# attiny-breakout.net
KiCad netlist of a schematic drawn in EAGLE
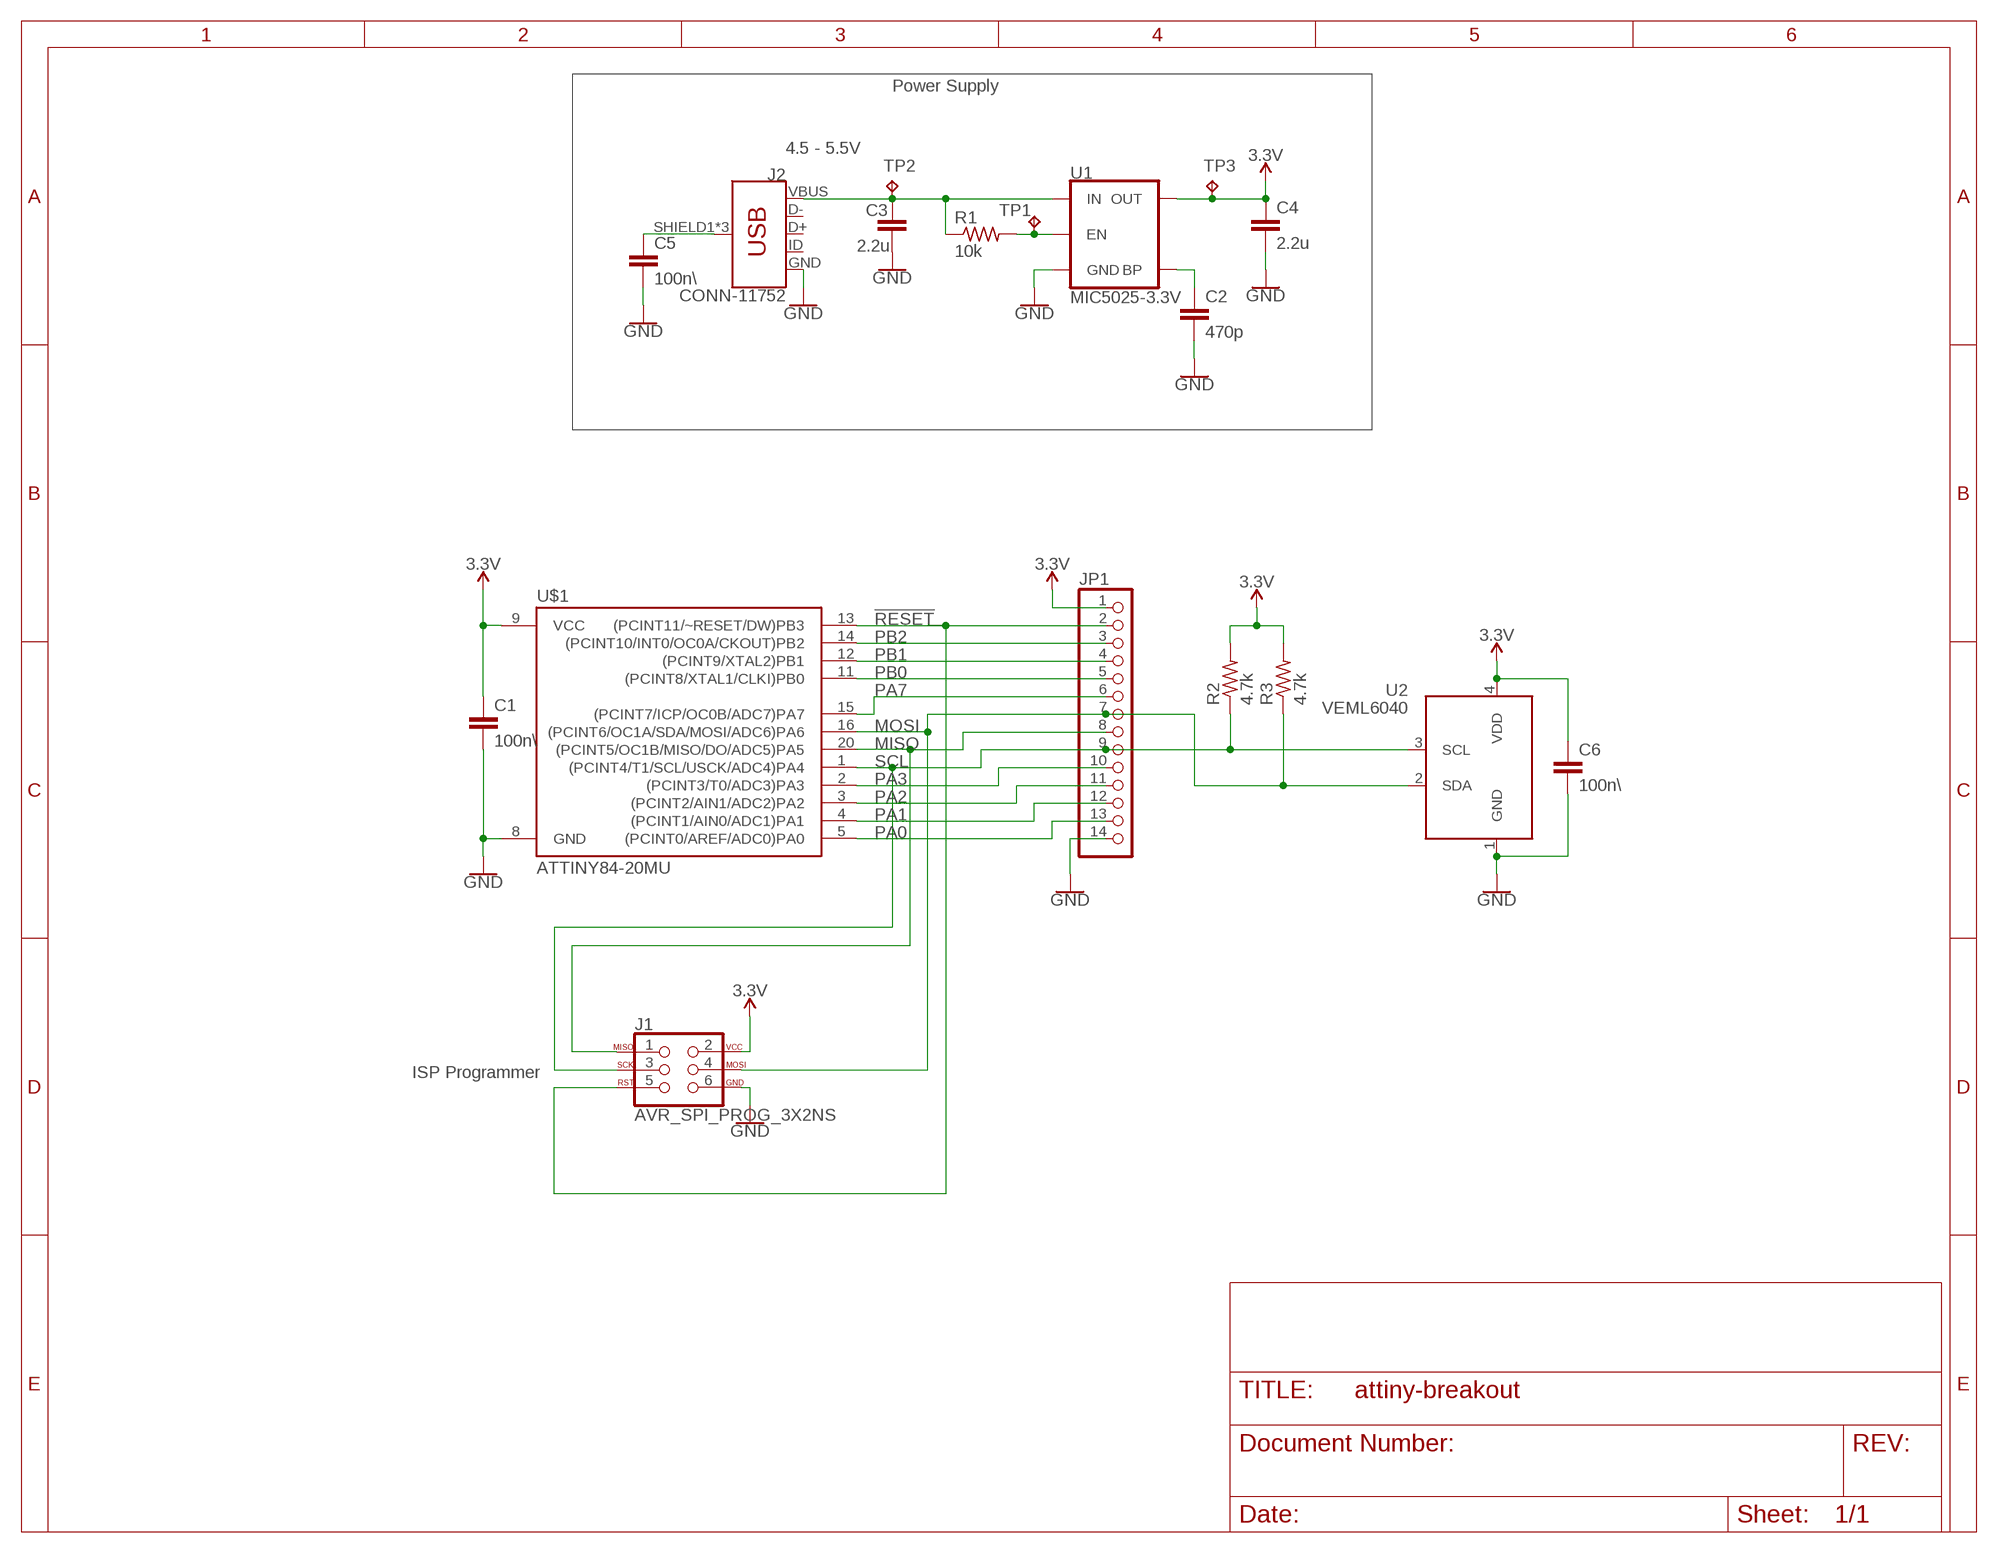
[diagram p0: schematic, sheet 1]

(export (version "E")
  (design (tool "Eeschema 10.0.6"))
  (components
    (comp (ref "C1")
      (value "100n\\")
      (footprint "eagle-import:C0805")
      (libsource (lib "eagle-import") (part "C-EUC0805"))
    )
    (comp (ref "C2")
      (value "470p")
      (footprint "eagle-import:C0805")
      (libsource (lib "eagle-import") (part "C-EUC0805"))
    )
    (comp (ref "C3")
      (value "2.2u")
      (footprint "eagle-import:C0805")
      (libsource (lib "eagle-import") (part "C-EUC0805"))
    )
    (comp (ref "C4")
      (value "2.2u")
      (footprint "eagle-import:C0805")
      (libsource (lib "eagle-import") (part "C-EUC0805"))
    )
    (comp (ref "C5")
      (value "100n\\")
      (footprint "eagle-import:C0805")
      (libsource (lib "eagle-import") (part "C-EUC0805"))
    )
    (comp (ref "C6")
      (value "100n\\")
      (footprint "eagle-import:C0805")
      (libsource (lib "eagle-import") (part "C-EUC0805"))
    )
    (comp (ref "J1")
      (value "AVR_SPI_PROG_3X2NS")
      (footprint "eagle-import:2X3-NS")
      (libsource (lib "eagle-import") (part "AVR_SPI_PROG_3X2NS"))
    )
    (comp (ref "J2")
      (value "CONN-11752")
      (footprint "eagle-import:USB-B-MICRO-SMD")
      (libsource (lib "eagle-import") (part "USB_MICRO-B_FEMALE-SMT"))
    )
    (comp (ref "JP1")
      (value "PINHD-1X14")
      (footprint "eagle-import:1X14")
      (libsource (lib "eagle-import") (part "PINHD-1X14"))
    )
    (comp (ref "R1")
      (value "10k")
      (footprint "eagle-import:R0805")
      (libsource (lib "eagle-import") (part "R-US_R0805"))
    )
    (comp (ref "R2")
      (value "4.7k")
      (footprint "eagle-import:R0805")
      (libsource (lib "eagle-import") (part "R-US_R0805"))
    )
    (comp (ref "R3")
      (value "4.7k")
      (footprint "eagle-import:R0805")
      (libsource (lib "eagle-import") (part "R-US_R0805"))
    )
    (comp (ref "TP1")
      (value "TPPAD1-13")
      (footprint "eagle-import:P1-13")
      (libsource (lib "eagle-import") (part "TPPAD1-13"))
    )
    (comp (ref "TP2")
      (value "TPPAD1-13")
      (footprint "eagle-import:P1-13")
      (libsource (lib "eagle-import") (part "TPPAD1-13"))
    )
    (comp (ref "TP3")
      (value "TPPAD1-13")
      (footprint "eagle-import:P1-13")
      (libsource (lib "eagle-import") (part "TPPAD1-13"))
    )
    (comp (ref "U$1")
      (value "ATTINY84-20MU")
      (footprint "eagle-import:QFN20")
      (libsource (lib "eagle-import") (part "ATTINY84ATTINY84-20MU"))
    )
    (comp (ref "U1")
      (value "MIC5025-3.3V")
      (footprint "eagle-import:SOT23-5")
      (libsource (lib "eagle-import") (part "V_REG_MIC52053.3V"))
    )
    (comp (ref "U2")
      (value "VEML6040")
      (footprint "eagle-import:VEML6040")
      (libsource (lib "eagle-import") (part "VEML6040"))
    )
  )
  (nets
    (net (code "1") (name "/MISO") (class "Default")
      (node (ref "J1") (pin "1") (pinfunction "1_1") (pintype "passive"))
      (node (ref "JP1") (pin "8") (pinfunction "8_8") (pintype "passive"))
      (node (ref "U$1") (pin "20") (pinfunction "(PCINT5/OC1B/MISO/DO/ADC5)PA5_20") (pintype "bidirectional"))
    )
    (net (code "2") (name "/MOSI") (class "Default")
      (node (ref "J1") (pin "4") (pinfunction "4_4") (pintype "passive"))
      (node (ref "JP1") (pin "7") (pinfunction "7_7") (pintype "passive"))
      (node (ref "R3") (pin "1") (pinfunction "1_1") (pintype "passive"))
      (node (ref "U$1") (pin "16") (pinfunction "(PCINT6/OC1A/SDA/MOSI/ADC6)PA6_16") (pintype "bidirectional"))
      (node (ref "U2") (pin "2") (pinfunction "SDA_2") (pintype "bidirectional"))
    )
    (net (code "3") (name "/PA0") (class "Default")
      (node (ref "JP1") (pin "13") (pinfunction "13_13") (pintype "passive"))
      (node (ref "U$1") (pin "5") (pinfunction "(PCINT0/AREF/ADC0)PA0_5") (pintype "bidirectional"))
    )
    (net (code "4") (name "/PA1") (class "Default")
      (node (ref "JP1") (pin "12") (pinfunction "12_12") (pintype "passive"))
      (node (ref "U$1") (pin "4") (pinfunction "(PCINT1/AIN0/ADC1)PA1_4") (pintype "bidirectional"))
    )
    (net (code "5") (name "/PA2") (class "Default")
      (node (ref "JP1") (pin "11") (pinfunction "11_11") (pintype "passive"))
      (node (ref "U$1") (pin "3") (pinfunction "(PCINT2/AIN1/ADC2)PA2_3") (pintype "bidirectional"))
    )
    (net (code "6") (name "/PA3") (class "Default")
      (node (ref "JP1") (pin "10") (pinfunction "10_10") (pintype "passive"))
      (node (ref "U$1") (pin "2") (pinfunction "(PCINT3/T0/ADC3)PA3_2") (pintype "bidirectional"))
    )
    (net (code "7") (name "/PA7") (class "Default")
      (node (ref "JP1") (pin "6") (pinfunction "6_6") (pintype "passive"))
      (node (ref "U$1") (pin "15") (pinfunction "(PCINT7/ICP/OC0B/ADC7)PA7_15") (pintype "bidirectional"))
    )
    (net (code "8") (name "/PB0") (class "Default")
      (node (ref "JP1") (pin "5") (pinfunction "5_5") (pintype "passive"))
      (node (ref "U$1") (pin "11") (pinfunction "(PCINT8/XTAL1/CLKI)PB0_11") (pintype "bidirectional"))
    )
    (net (code "9") (name "/PB1") (class "Default")
      (node (ref "JP1") (pin "4") (pinfunction "4_4") (pintype "passive"))
      (node (ref "U$1") (pin "12") (pinfunction "(PCINT9/XTAL2)PB1_12") (pintype "bidirectional"))
    )
    (net (code "10") (name "/PB2") (class "Default")
      (node (ref "JP1") (pin "3") (pinfunction "3_3") (pintype "passive"))
      (node (ref "U$1") (pin "14") (pinfunction "(PCINT10/INT0/OC0A/CKOUT)PB2_14") (pintype "bidirectional"))
    )
    (net (code "11") (name "/SCL") (class "Default")
      (node (ref "J1") (pin "3") (pinfunction "3_3") (pintype "passive"))
      (node (ref "JP1") (pin "9") (pinfunction "9_9") (pintype "passive"))
      (node (ref "R2") (pin "1") (pinfunction "1_1") (pintype "passive"))
      (node (ref "U$1") (pin "1") (pinfunction "(PCINT4/T1/SCL/USCK/ADC4)PA4_1") (pintype "bidirectional"))
      (node (ref "U2") (pin "3") (pinfunction "SCL_3") (pintype "input"))
    )
    (net (code "12") (name "/~{RESET}") (class "Default")
      (node (ref "J1") (pin "5") (pinfunction "5_5") (pintype "passive"))
      (node (ref "JP1") (pin "2") (pinfunction "2_2") (pintype "passive"))
      (node (ref "U$1") (pin "13") (pinfunction "(PCINT11/~{RESET/DW})PB3_13") (pintype "bidirectional"))
    )
    (net (code "13") (name "3.3V") (class "Default")
      (node (ref "C1") (pin "1") (pinfunction "1_1") (pintype "passive"))
      (node (ref "C4") (pin "1") (pinfunction "1_1") (pintype "passive"))
      (node (ref "C6") (pin "1") (pinfunction "1_1") (pintype "passive"))
      (node (ref "J1") (pin "2") (pinfunction "2_2") (pintype "passive"))
      (node (ref "JP1") (pin "1") (pinfunction "1_1") (pintype "passive"))
      (node (ref "R2") (pin "2") (pinfunction "2_2") (pintype "passive"))
      (node (ref "R3") (pin "2") (pinfunction "2_2") (pintype "passive"))
      (node (ref "TP3") (pin "TP") (pinfunction "TP_TP") (pintype "input"))
      (node (ref "U$1") (pin "9") (pinfunction "VCC_9") (pintype "bidirectional"))
      (node (ref "U1") (pin "5") (pinfunction "OUT_5") (pintype "passive"))
      (node (ref "U2") (pin "4") (pinfunction "VDD_4") (pintype "power_in"))
    )
    (net (code "14") (name "GND") (class "Default")
      (node (ref "C1") (pin "2") (pinfunction "2_2") (pintype "passive"))
      (node (ref "C2") (pin "2") (pinfunction "2_2") (pintype "passive"))
      (node (ref "C3") (pin "2") (pinfunction "2_2") (pintype "passive"))
      (node (ref "C4") (pin "2") (pinfunction "2_2") (pintype "passive"))
      (node (ref "C5") (pin "2") (pinfunction "2_2") (pintype "passive"))
      (node (ref "C6") (pin "2") (pinfunction "2_2") (pintype "passive"))
      (node (ref "J1") (pin "6") (pinfunction "6_6") (pintype "passive"))
      (node (ref "J2") (pin "GND") (pinfunction "GND_GND") (pintype "power_in"))
      (node (ref "JP1") (pin "14") (pinfunction "14_14") (pintype "passive"))
      (node (ref "U$1") (pin "8") (pinfunction "GND_8") (pintype "bidirectional"))
      (node (ref "U1") (pin "2") (pinfunction "GND_2") (pintype "input"))
      (node (ref "U2") (pin "1") (pinfunction "GND_1") (pintype "power_in"))
    )
    (net (code "15") (name "Net-(C5-Pad1)") (class "Default")
      (node (ref "C5") (pin "1") (pinfunction "1_1") (pintype "passive"))
      (node (ref "J2") (pin "SHIELD1") (pinfunction "SHIELD_SHIELD1") (pintype "bidirectional"))
      (node (ref "J2") (pin "SHIELD2") (pinfunction "SHIELD_SHIELD2") (pintype "bidirectional"))
      (node (ref "J2") (pin "SHIELD3") (pinfunction "SHIELD_SHIELD3") (pintype "bidirectional"))
    )
    (net (code "16") (name "Net-(U1-BP)") (class "Default")
      (node (ref "C2") (pin "1") (pinfunction "1_1") (pintype "passive"))
      (node (ref "U1") (pin "4") (pinfunction "BP_4") (pintype "input"))
    )
    (net (code "17") (name "Net-(U1-EN)") (class "Default")
      (node (ref "R1") (pin "2") (pinfunction "2_2") (pintype "passive"))
      (node (ref "TP1") (pin "TP") (pinfunction "TP_TP") (pintype "input"))
      (node (ref "U1") (pin "3") (pinfunction "EN_3") (pintype "input"))
    )
    (net (code "18") (name "Net-(U1-IN)") (class "Default")
      (node (ref "C3") (pin "1") (pinfunction "1_1") (pintype "passive"))
      (node (ref "J2") (pin "VBUS") (pinfunction "VBUS_VBUS") (pintype "power_in"))
      (node (ref "R1") (pin "1") (pinfunction "1_1") (pintype "passive"))
      (node (ref "TP2") (pin "TP") (pinfunction "TP_TP") (pintype "input"))
      (node (ref "U1") (pin "1") (pinfunction "IN_1") (pintype "input"))
    )
    (net (code "19") (name "unconnected-(J2-PadD+)") (class "Default")
      (node (ref "J2") (pin "D+") (pinfunction "D+_D+") (pintype "bidirectional"))
    )
    (net (code "20") (name "unconnected-(J2-PadD-)") (class "Default")
      (node (ref "J2") (pin "D-") (pinfunction "D-_D-") (pintype "bidirectional"))
    )
    (net (code "21") (name "unconnected-(J2-PadID)") (class "Default")
      (node (ref "J2") (pin "ID") (pinfunction "ID_ID") (pintype "bidirectional"))
    )
  )
)
